# Plasma_Speaker_H-Bridge.net
KiCad netlist of a schematic drawn in Altium Designer
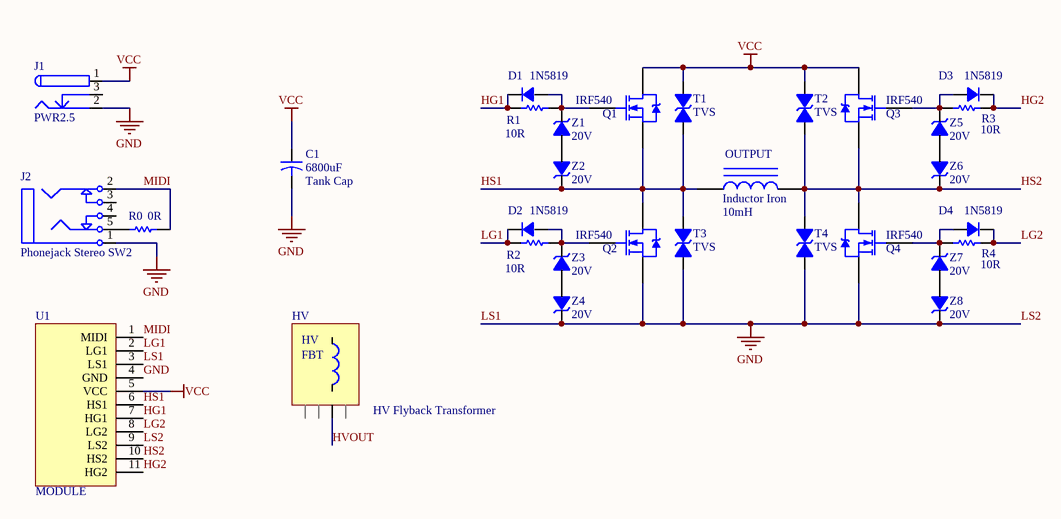
[diagram p0: Plasma Speaker H-Bridge.SchDoc]

(export (version "E")
  (design (tool "Eeschema 10.0.6"))
  (components
    (comp (ref "C1")
      (value "Tank Cap")
      (footprint "RB7.5H30")
      (description "Capacitor")
      (fields (field (name "ALTIUM_VALUE") "6800uF") (field (name "PUBLISHER") "Altium Limited"))
      (libsource (lib "Miscellaneous Devices") (part "Cap2"))
    )
    (comp (ref "D1")
      (value "1N5819")
      (footprint "DO-214")
      (description "Zener Diode")
      (fields (field (name "PUBLISHER") "Altium Limited"))
      (libsource (lib "Miscellaneous Devices") (part "Diode S"))
    )
    (comp (ref "D2")
      (value "1N5819")
      (footprint "DO-214")
      (description "Zener Diode")
      (fields (field (name "PUBLISHER") "Altium Limited"))
      (libsource (lib "Miscellaneous Devices") (part "Diode S"))
    )
    (comp (ref "D3")
      (value "1N5819")
      (footprint "DO-214")
      (description "Zener Diode")
      (fields (field (name "PUBLISHER") "Altium Limited"))
      (libsource (lib "Miscellaneous Devices") (part "Diode S"))
    )
    (comp (ref "D4")
      (value "1N5819")
      (footprint "DO-214")
      (description "Zener Diode")
      (fields (field (name "PUBLISHER") "Altium Limited"))
      (libsource (lib "Miscellaneous Devices") (part "Diode S"))
    )
    (comp (ref "HV")
      (value "HV Flyback Transformer")
      (footprint "154-207E")
      (libsource (lib "Modules") (part "154-207E FBT"))
    )
    (comp (ref "J1")
      (value "PWR2.5")
      (footprint "2.5 PWR")
      (description "Low Voltage Power Supply Connector")
      (fields (field (name "PUBLISHER") "Altium Limited"))
      (libsource (lib "Miscellaneous Connectors") (part "PWR2.5"))
    )
    (comp (ref "J2")
      (value "Phonejack Stereo SW2")
      (footprint "Phonejack Type-1")
      (description "3-Conductor Jack with 2 break contacts (normals) and 2 auxiliary make contacts")
      (fields (field (name "PUBLISHER") "Altium Limited"))
      (libsource (lib "Miscellaneous Connectors") (part "Phonejack Stereo SW2"))
    )
    (comp (ref "OUTPUT")
      (value "Inductor Iron")
      (footprint "CON-3.0")
      (description "Magnetic-Core Inductor")
      (fields (field (name "ALTIUM_VALUE") "10mH") (field (name "PUBLISHER") "Altium Limited"))
      (libsource (lib "Miscellaneous Devices") (part "Inductor Iron"))
    )
    (comp (ref "Q1")
      (value "IRF540")
      (footprint "TO-263")
      (description "N-Channel Power MOSFET")
      (fields (field (name "PUBLISHER") "Altium Limited"))
      (libsource (lib "Miscellaneous Devices") (part "NMOS-2"))
    )
    (comp (ref "Q2")
      (value "IRF540")
      (footprint "TO-263")
      (description "N-Channel Power MOSFET")
      (fields (field (name "PUBLISHER") "Altium Limited"))
      (libsource (lib "Miscellaneous Devices") (part "NMOS-2"))
    )
    (comp (ref "Q3")
      (value "IRF540")
      (footprint "TO-263")
      (description "N-Channel Power MOSFET")
      (fields (field (name "PUBLISHER") "Altium Limited"))
      (libsource (lib "Miscellaneous Devices") (part "NMOS-2"))
    )
    (comp (ref "Q4")
      (value "IRF540")
      (footprint "TO-263")
      (description "N-Channel Power MOSFET")
      (fields (field (name "PUBLISHER") "Altium Limited"))
      (libsource (lib "Miscellaneous Devices") (part "NMOS-2"))
    )
    (comp (ref "R0")
      (value "0R")
      (footprint "D0805")
      (description "Resistor")
      (fields (field (name "Comment") "0603") (field (name "PUBLISHER") "Altium Limited"))
      (libsource (lib "Miscellaneous Devices") (part "Res1"))
    )
    (comp (ref "R1")
      (value "10R")
      (footprint "D1206")
      (description "Resistor")
      (fields (field (name "Comment") "1206") (field (name "PUBLISHER") "Altium Limited"))
      (libsource (lib "Miscellaneous Devices") (part "Res1"))
    )
    (comp (ref "R2")
      (value "10R")
      (footprint "D1206")
      (description "Resistor")
      (fields (field (name "Comment") "1206") (field (name "PUBLISHER") "Altium Limited"))
      (libsource (lib "Miscellaneous Devices") (part "Res1"))
    )
    (comp (ref "R3")
      (value "10R")
      (footprint "D1206")
      (description "Resistor")
      (fields (field (name "Comment") "1206") (field (name "PUBLISHER") "Altium Limited"))
      (libsource (lib "Miscellaneous Devices") (part "Res1"))
    )
    (comp (ref "R4")
      (value "10R")
      (footprint "D1206")
      (description "Resistor")
      (fields (field (name "Comment") "1206") (field (name "PUBLISHER") "Altium Limited"))
      (libsource (lib "Miscellaneous Devices") (part "Res1"))
    )
    (comp (ref "T1")
      (value "TVS")
      (footprint "DO-214")
      (description "TVS Diode")
      (fields (field (name "PUBLISHER") "Altium Limited"))
      (libsource (lib "Miscellaneous Devices") (part "TVS Diode"))
    )
    (comp (ref "T2")
      (value "TVS")
      (footprint "DO-214")
      (description "TVS Diode")
      (fields (field (name "PUBLISHER") "Altium Limited"))
      (libsource (lib "Miscellaneous Devices") (part "TVS Diode"))
    )
    (comp (ref "T3")
      (value "TVS")
      (footprint "DO-214")
      (description "TVS Diode")
      (fields (field (name "PUBLISHER") "Altium Limited"))
      (libsource (lib "Miscellaneous Devices") (part "TVS Diode"))
    )
    (comp (ref "T4")
      (value "TVS")
      (footprint "DO-214")
      (description "TVS Diode")
      (fields (field (name "PUBLISHER") "Altium Limited"))
      (libsource (lib "Miscellaneous Devices") (part "TVS Diode"))
    )
    (comp (ref "U1")
      (value "MODULE")
      (footprint "Plasma Speaker Module")
      (description "Plasma Speaker Signal Module")
      (libsource (lib "Modules") (part "Plasma Speaker"))
    )
    (comp (ref "Z1")
      (value "20V")
      (footprint "D1206")
      (description "Zener Diode")
      (fields (field (name "PUBLISHER") "Altium Limited"))
      (libsource (lib "Miscellaneous Devices") (part "Zener"))
    )
    (comp (ref "Z2")
      (value "20V")
      (footprint "D1206")
      (description "Zener Diode")
      (fields (field (name "PUBLISHER") "Altium Limited"))
      (libsource (lib "Miscellaneous Devices") (part "Zener"))
    )
    (comp (ref "Z3")
      (value "20V")
      (footprint "D1206")
      (description "Zener Diode")
      (fields (field (name "PUBLISHER") "Altium Limited"))
      (libsource (lib "Miscellaneous Devices") (part "Zener"))
    )
    (comp (ref "Z4")
      (value "20V")
      (footprint "D1206")
      (description "Zener Diode")
      (fields (field (name "PUBLISHER") "Altium Limited"))
      (libsource (lib "Miscellaneous Devices") (part "Zener"))
    )
    (comp (ref "Z5")
      (value "20V")
      (footprint "D1206")
      (description "Zener Diode")
      (fields (field (name "PUBLISHER") "Altium Limited"))
      (libsource (lib "Miscellaneous Devices") (part "Zener"))
    )
    (comp (ref "Z6")
      (value "20V")
      (footprint "D1206")
      (description "Zener Diode")
      (fields (field (name "PUBLISHER") "Altium Limited"))
      (libsource (lib "Miscellaneous Devices") (part "Zener"))
    )
    (comp (ref "Z7")
      (value "20V")
      (footprint "D1206")
      (description "Zener Diode")
      (fields (field (name "PUBLISHER") "Altium Limited"))
      (libsource (lib "Miscellaneous Devices") (part "Zener"))
    )
    (comp (ref "Z8")
      (value "20V")
      (footprint "D1206")
      (description "Zener Diode")
      (fields (field (name "PUBLISHER") "Altium Limited"))
      (libsource (lib "Miscellaneous Devices") (part "Zener"))
    )
  )
  (nets
    (net (code "1") (name "/HG1") (class "Default")
      (node (ref "D1") (pin "2") (pinfunction "2_2") (pintype "passive"))
      (node (ref "R1") (pin "1") (pinfunction "1_1") (pintype "passive"))
      (node (ref "U1") (pin "7") (pinfunction "HG1_7") (pintype "passive"))
    )
    (net (code "2") (name "/HG2") (class "Default")
      (node (ref "D3") (pin "2") (pinfunction "2_2") (pintype "passive"))
      (node (ref "R3") (pin "2") (pinfunction "2_2") (pintype "passive"))
      (node (ref "U1") (pin "11") (pinfunction "HG2_11") (pintype "passive"))
    )
    (net (code "3") (name "/HS1") (class "Default")
      (node (ref "OUTPUT") (pin "1") (pinfunction "1_1") (pintype "passive"))
      (node (ref "Q1") (pin "3") (pinfunction "S_3") (pintype "passive"))
      (node (ref "Q2") (pin "2") (pinfunction "D_2") (pintype "passive"))
      (node (ref "T1") (pin "1") (pinfunction "1_1") (pintype "passive"))
      (node (ref "T3") (pin "2") (pinfunction "2_2") (pintype "passive"))
      (node (ref "U1") (pin "6") (pinfunction "HS1_6") (pintype "passive"))
      (node (ref "Z2") (pin "2") (pinfunction "2_2") (pintype "passive"))
    )
    (net (code "4") (name "/HS2") (class "Default")
      (node (ref "OUTPUT") (pin "2") (pinfunction "2_2") (pintype "passive"))
      (node (ref "Q3") (pin "3") (pinfunction "S_3") (pintype "passive"))
      (node (ref "Q4") (pin "2") (pinfunction "D_2") (pintype "passive"))
      (node (ref "T2") (pin "1") (pinfunction "1_1") (pintype "passive"))
      (node (ref "T4") (pin "2") (pinfunction "2_2") (pintype "passive"))
      (node (ref "U1") (pin "10") (pinfunction "HS2_10") (pintype "passive"))
      (node (ref "Z6") (pin "2") (pinfunction "2_2") (pintype "passive"))
    )
    (net (code "5") (name "/HVOUT") (class "Default")
      (node (ref "HV") (pin "1") (pinfunction "1_1") (pintype "passive"))
    )
    (net (code "6") (name "/LG1") (class "Default")
      (node (ref "D2") (pin "2") (pinfunction "2_2") (pintype "passive"))
      (node (ref "R2") (pin "1") (pinfunction "1_1") (pintype "passive"))
      (node (ref "U1") (pin "2") (pinfunction "LG1_2") (pintype "passive"))
    )
    (net (code "7") (name "/LG2") (class "Default")
      (node (ref "D4") (pin "2") (pinfunction "2_2") (pintype "passive"))
      (node (ref "R4") (pin "2") (pinfunction "2_2") (pintype "passive"))
      (node (ref "U1") (pin "8") (pinfunction "LG2_8") (pintype "passive"))
    )
    (net (code "8") (name "/MIDI") (class "Default")
      (node (ref "J2") (pin "2") (pinfunction "2_2") (pintype "passive"))
      (node (ref "R0") (pin "2") (pinfunction "2_2") (pintype "passive"))
      (node (ref "U1") (pin "1") (pinfunction "MIDI_1") (pintype "passive"))
    )
    (net (code "9") (name "GND") (class "Default")
      (node (ref "C1") (pin "2") (pinfunction "2_2") (pintype "passive"))
      (node (ref "J1") (pin "2") (pinfunction "2_2") (pintype "power_in"))
      (node (ref "J2") (pin "1") (pinfunction "1_1") (pintype "passive"))
      (node (ref "Q2") (pin "3") (pinfunction "S_3") (pintype "passive"))
      (node (ref "Q4") (pin "3") (pinfunction "S_3") (pintype "passive"))
      (node (ref "T3") (pin "1") (pinfunction "1_1") (pintype "passive"))
      (node (ref "T4") (pin "1") (pinfunction "1_1") (pintype "passive"))
      (node (ref "U1") (pin "3") (pinfunction "LS1_3") (pintype "passive"))
      (node (ref "U1") (pin "4") (pinfunction "GND_4") (pintype "passive"))
      (node (ref "U1") (pin "9") (pinfunction "LS2_9") (pintype "passive"))
      (node (ref "Z4") (pin "2") (pinfunction "2_2") (pintype "passive"))
      (node (ref "Z8") (pin "2") (pinfunction "2_2") (pintype "passive"))
    )
    (net (code "10") (name "Net-(J2-Pad5)") (class "Default")
      (node (ref "J2") (pin "5") (pinfunction "5_5") (pintype "passive"))
      (node (ref "R0") (pin "1") (pinfunction "1_1") (pintype "passive"))
    )
    (net (code "11") (name "Net-(Q1-G)") (class "Default")
      (node (ref "D1") (pin "1") (pinfunction "1_1") (pintype "passive"))
      (node (ref "Q1") (pin "1") (pinfunction "G_1") (pintype "passive"))
      (node (ref "R1") (pin "2") (pinfunction "2_2") (pintype "passive"))
      (node (ref "Z1") (pin "2") (pinfunction "2_2") (pintype "passive"))
    )
    (net (code "12") (name "Net-(Q2-G)") (class "Default")
      (node (ref "D2") (pin "1") (pinfunction "1_1") (pintype "passive"))
      (node (ref "Q2") (pin "1") (pinfunction "G_1") (pintype "passive"))
      (node (ref "R2") (pin "2") (pinfunction "2_2") (pintype "passive"))
      (node (ref "Z3") (pin "2") (pinfunction "2_2") (pintype "passive"))
    )
    (net (code "13") (name "Net-(Q3-G)") (class "Default")
      (node (ref "D3") (pin "1") (pinfunction "1_1") (pintype "passive"))
      (node (ref "Q3") (pin "1") (pinfunction "G_1") (pintype "passive"))
      (node (ref "R3") (pin "1") (pinfunction "1_1") (pintype "passive"))
      (node (ref "Z5") (pin "2") (pinfunction "2_2") (pintype "passive"))
    )
    (net (code "14") (name "Net-(Q4-G)") (class "Default")
      (node (ref "D4") (pin "1") (pinfunction "1_1") (pintype "passive"))
      (node (ref "Q4") (pin "1") (pinfunction "G_1") (pintype "passive"))
      (node (ref "R4") (pin "1") (pinfunction "1_1") (pintype "passive"))
      (node (ref "Z7") (pin "2") (pinfunction "2_2") (pintype "passive"))
    )
    (net (code "15") (name "Net-(Z1-Pad1)") (class "Default")
      (node (ref "Z1") (pin "1") (pinfunction "1_1") (pintype "passive"))
      (node (ref "Z2") (pin "1") (pinfunction "1_1") (pintype "passive"))
    )
    (net (code "16") (name "Net-(Z3-Pad1)") (class "Default")
      (node (ref "Z3") (pin "1") (pinfunction "1_1") (pintype "passive"))
      (node (ref "Z4") (pin "1") (pinfunction "1_1") (pintype "passive"))
    )
    (net (code "17") (name "Net-(Z5-Pad1)") (class "Default")
      (node (ref "Z5") (pin "1") (pinfunction "1_1") (pintype "passive"))
      (node (ref "Z6") (pin "1") (pinfunction "1_1") (pintype "passive"))
    )
    (net (code "18") (name "Net-(Z7-Pad1)") (class "Default")
      (node (ref "Z7") (pin "1") (pinfunction "1_1") (pintype "passive"))
      (node (ref "Z8") (pin "1") (pinfunction "1_1") (pintype "passive"))
    )
    (net (code "19") (name "VCC") (class "Default")
      (node (ref "C1") (pin "1") (pinfunction "1_1") (pintype "passive"))
      (node (ref "J1") (pin "1") (pinfunction "1_1") (pintype "power_in"))
      (node (ref "Q1") (pin "2") (pinfunction "D_2") (pintype "passive"))
      (node (ref "Q3") (pin "2") (pinfunction "D_2") (pintype "passive"))
      (node (ref "T1") (pin "2") (pinfunction "2_2") (pintype "passive"))
      (node (ref "T2") (pin "2") (pinfunction "2_2") (pintype "passive"))
      (node (ref "U1") (pin "5") (pinfunction "VCC_5") (pintype "passive"))
    )
    (net (code "20") (name "unconnected-(J1-Pad3)") (class "Default")
      (node (ref "J1") (pin "3") (pinfunction "3_3") (pintype "power_in"))
    )
    (net (code "21") (name "unconnected-(J2-Pad3)") (class "Default")
      (node (ref "J2") (pin "3") (pinfunction "3_3") (pintype "passive"))
    )
    (net (code "22") (name "unconnected-(J2-Pad4)") (class "Default")
      (node (ref "J2") (pin "4") (pinfunction "4_4") (pintype "passive"))
    )
  )
)
